# PIC18f26k40_TPLinkBackpack.net
KiCad netlist of a schematic drawn in EAGLE
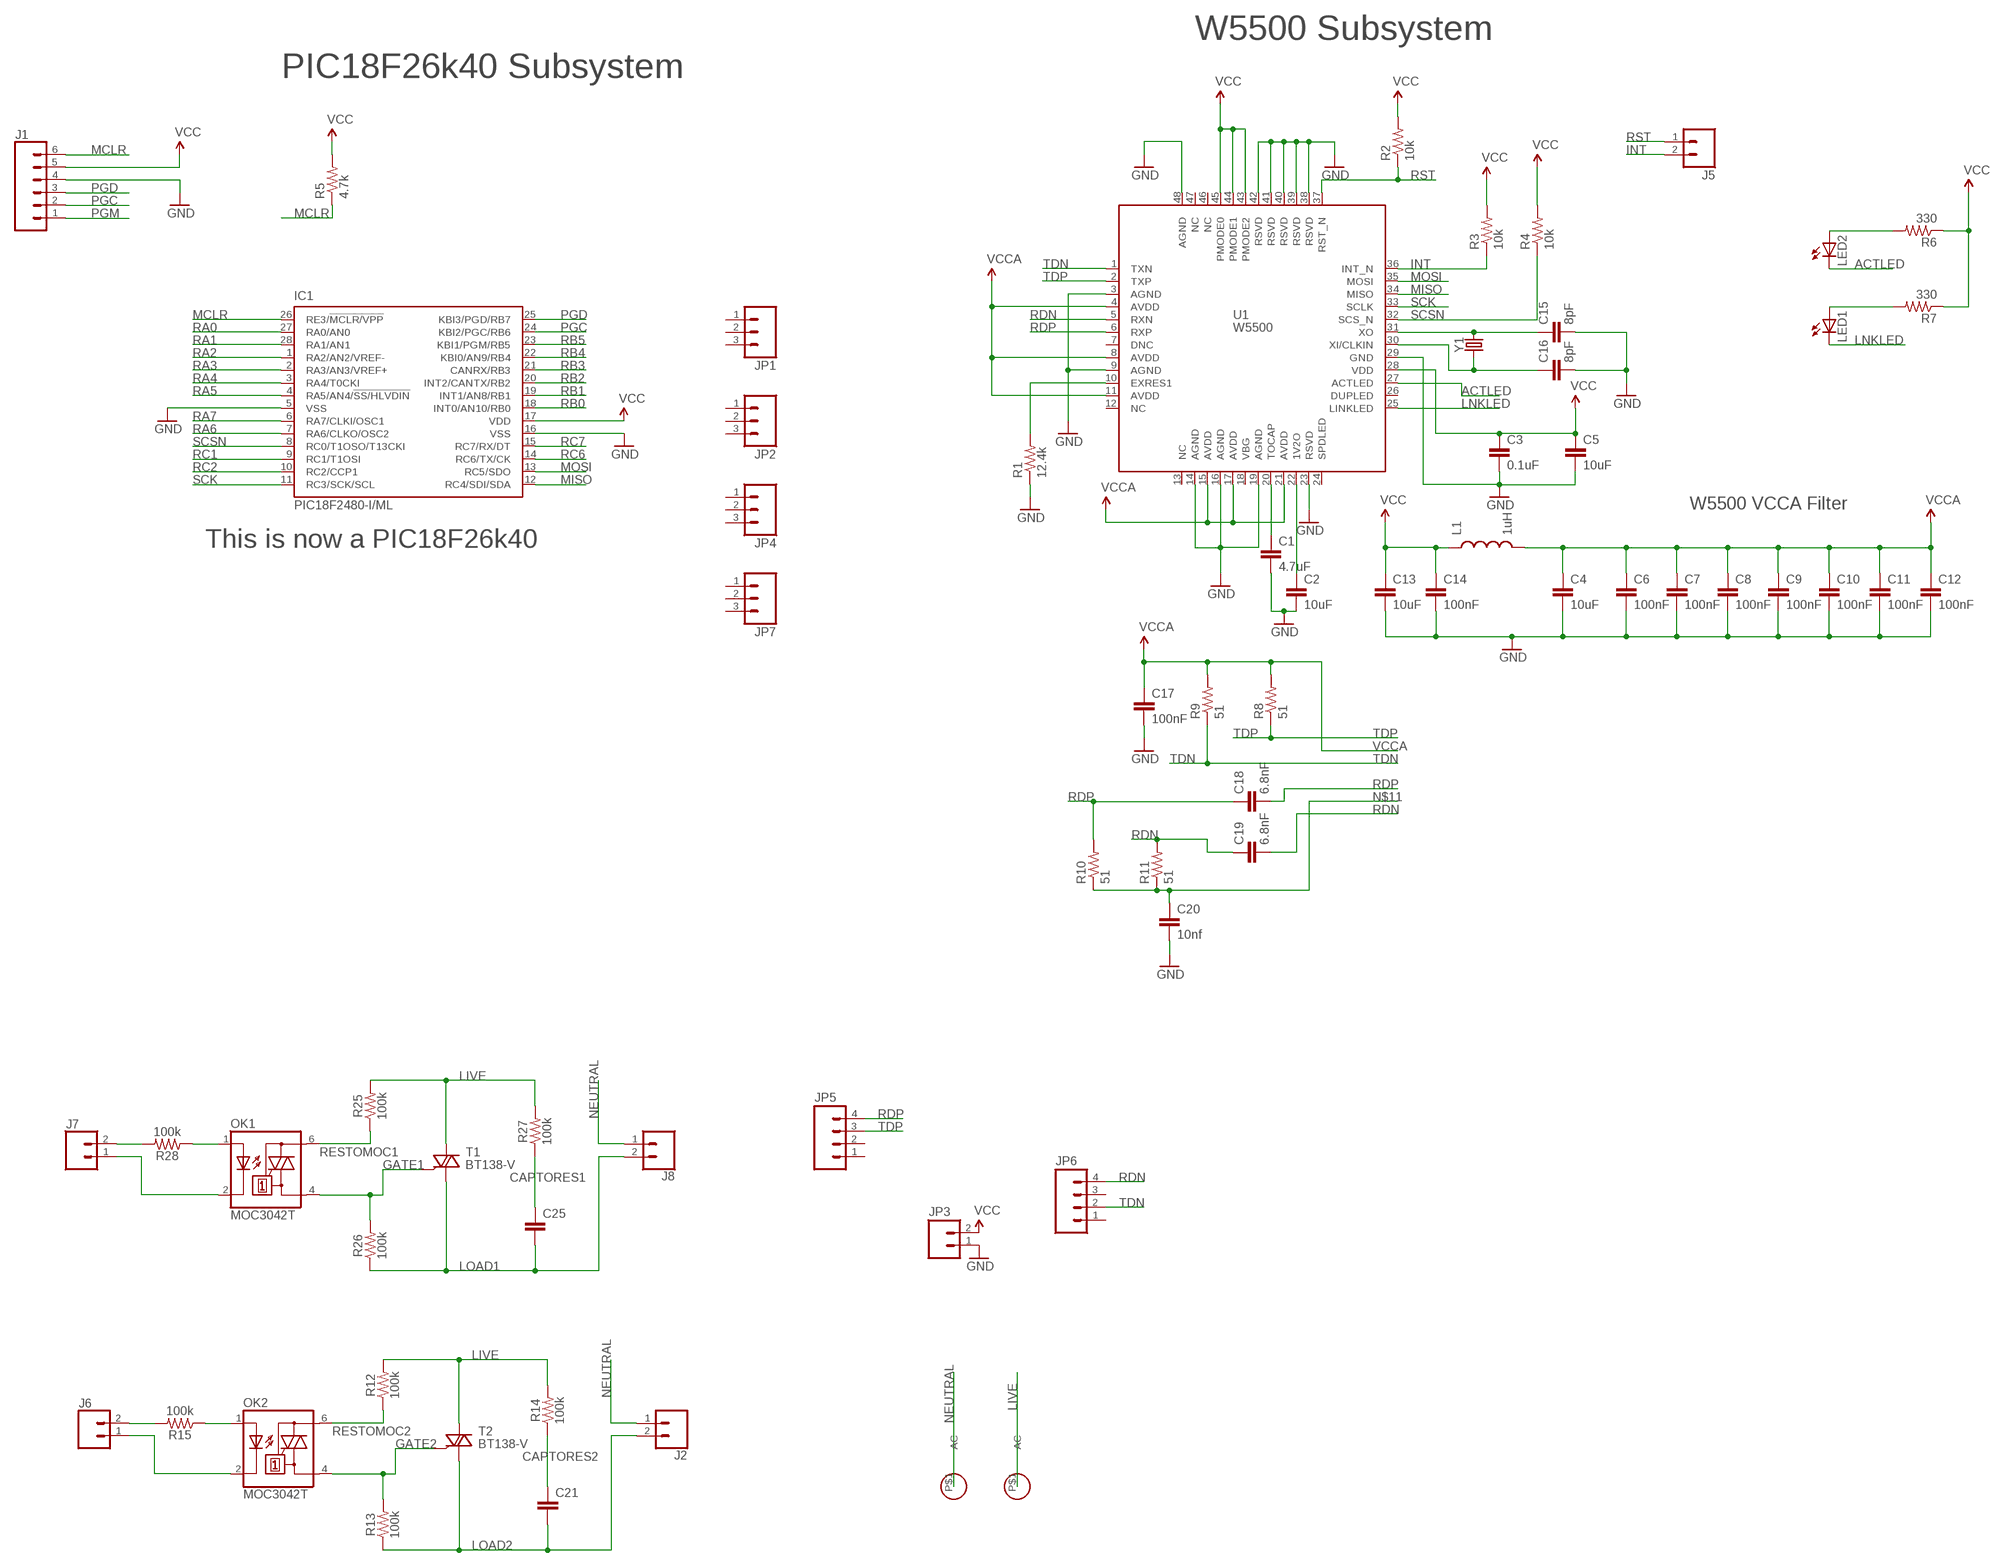
[diagram p0: schematic, sheet 1]

(export (version "E")
  (design (tool "Eeschema 10.0.6"))
  (components
    (comp (ref "AC_L")
      (value "AC_BLADE")
      (footprint "eagle-import:AC_BLADE")
      (libsource (lib "eagle-import") (part "AC_BLADE"))
    )
    (comp (ref "AC_N")
      (value "AC_BLADE")
      (footprint "eagle-import:AC_BLADE")
      (libsource (lib "eagle-import") (part "AC_BLADE"))
    )
    (comp (ref "C1")
      (value "4.7uF")
      (footprint "eagle-import:0603-CAP")
      (libsource (lib "eagle-import") (part "SparkFun-Passives_CAP0603-CAP"))
    )
    (comp (ref "C2")
      (value "10uF")
      (footprint "eagle-import:0603-CAP")
      (libsource (lib "eagle-import") (part "SparkFun-Passives_CAP0603-CAP"))
    )
    (comp (ref "C3")
      (value "0.1uF")
      (footprint "eagle-import:0603-CAP")
      (libsource (lib "eagle-import") (part "SparkFun-Passives_CAP0603-CAP"))
    )
    (comp (ref "C4")
      (value "10uF")
      (footprint "eagle-import:0603-CAP")
      (libsource (lib "eagle-import") (part "SparkFun-Passives_CAP0603-CAP"))
    )
    (comp (ref "C5")
      (value "10uF")
      (footprint "eagle-import:0603-CAP")
      (libsource (lib "eagle-import") (part "SparkFun-Passives_CAP0603-CAP"))
    )
    (comp (ref "C6")
      (value "100nF")
      (footprint "eagle-import:0603-CAP")
      (libsource (lib "eagle-import") (part "SparkFun-Passives_CAP0603-CAP"))
    )
    (comp (ref "C7")
      (value "100nF")
      (footprint "eagle-import:0603-CAP")
      (libsource (lib "eagle-import") (part "SparkFun-Passives_CAP0603-CAP"))
    )
    (comp (ref "C8")
      (value "100nF")
      (footprint "eagle-import:0603-CAP")
      (libsource (lib "eagle-import") (part "SparkFun-Passives_CAP0603-CAP"))
    )
    (comp (ref "C9")
      (value "100nF")
      (footprint "eagle-import:0603-CAP")
      (libsource (lib "eagle-import") (part "SparkFun-Passives_CAP0603-CAP"))
    )
    (comp (ref "C10")
      (value "100nF")
      (footprint "eagle-import:0603-CAP")
      (libsource (lib "eagle-import") (part "SparkFun-Passives_CAP0603-CAP"))
    )
    (comp (ref "C11")
      (value "100nF")
      (footprint "eagle-import:0603-CAP")
      (libsource (lib "eagle-import") (part "SparkFun-Passives_CAP0603-CAP"))
    )
    (comp (ref "C12")
      (value "100nF")
      (footprint "eagle-import:0603-CAP")
      (libsource (lib "eagle-import") (part "SparkFun-Passives_CAP0603-CAP"))
    )
    (comp (ref "C13")
      (value "10uF")
      (footprint "eagle-import:0603-CAP")
      (libsource (lib "eagle-import") (part "SparkFun-Passives_CAP0603-CAP"))
    )
    (comp (ref "C14")
      (value "100nF")
      (footprint "eagle-import:0603-CAP")
      (libsource (lib "eagle-import") (part "SparkFun-Passives_CAP0603-CAP"))
    )
    (comp (ref "C15")
      (value "8pF")
      (footprint "eagle-import:0603-CAP")
      (libsource (lib "eagle-import") (part "SparkFun-Passives_CAP0603-CAP"))
    )
    (comp (ref "C16")
      (value "8pF")
      (footprint "eagle-import:0603-CAP")
      (libsource (lib "eagle-import") (part "SparkFun-Passives_CAP0603-CAP"))
    )
    (comp (ref "C17")
      (value "100nF")
      (footprint "eagle-import:0603-CAP")
      (libsource (lib "eagle-import") (part "SparkFun-Passives_CAP0603-CAP"))
    )
    (comp (ref "C18")
      (value "6.8nF")
      (footprint "eagle-import:0603-CAP")
      (libsource (lib "eagle-import") (part "SparkFun-Passives_CAP0603-CAP"))
    )
    (comp (ref "C19")
      (value "6.8nF")
      (footprint "eagle-import:0603-CAP")
      (libsource (lib "eagle-import") (part "SparkFun-Passives_CAP0603-CAP"))
    )
    (comp (ref "C20")
      (value "10nf")
      (footprint "eagle-import:0603-CAP")
      (libsource (lib "eagle-import") (part "SparkFun-Passives_CAP0603-CAP"))
    )
    (comp (ref "C21")
      (value "CAP0603-CAP")
      (footprint "eagle-import:0603-CAP")
      (libsource (lib "eagle-import") (part "CAP0603-CAP"))
    )
    (comp (ref "C25")
      (value "CAP0603-CAP")
      (footprint "eagle-import:0603-CAP")
      (libsource (lib "eagle-import") (part "CAP0603-CAP"))
    )
    (comp (ref "IC1")
      (value "PIC18F2480-I/ML")
      (footprint "eagle-import:QFN28-ML_6X6MM")
      (fields (field (name "MF") "MICROCHIP"))
      (libsource (lib "eagle-import") (part "PIC18F280-I/ML4"))
    )
    (comp (ref "J1")
      (value "CONN_06NO_SILK_FEMALE_PTH")
      (footprint "eagle-import:1X06_NO_SILK")
      (libsource (lib "eagle-import") (part "CONN_06NO_SILK_FEMALE_PTH"))
    )
    (comp (ref "J2")
      (value "CONN_025MM")
      (footprint "eagle-import:SCREWTERMINAL-5MM-2")
      (libsource (lib "eagle-import") (part "CONN_025MM"))
    )
    (comp (ref "J5")
      (value "M02PTH")
      (footprint "eagle-import:1X02@1")
      (libsource (lib "eagle-import") (part "M02PTH"))
    )
    (comp (ref "J6")
      (value "CONN_02")
      (footprint "eagle-import:1X02")
      (libsource (lib "eagle-import") (part "CONN_02"))
    )
    (comp (ref "J7")
      (value "CONN_02")
      (footprint "eagle-import:1X02")
      (libsource (lib "eagle-import") (part "CONN_02"))
    )
    (comp (ref "J8")
      (value "CONN_025MM")
      (footprint "eagle-import:SCREWTERMINAL-5MM-2")
      (libsource (lib "eagle-import") (part "CONN_025MM"))
    )
    (comp (ref "JP1")
      (value "M03LONGPADS")
      (footprint "eagle-import:1X03_LONGPADS")
      (libsource (lib "eagle-import") (part "M03LONGPADS"))
    )
    (comp (ref "JP2")
      (value "M03LONGPADS")
      (footprint "eagle-import:1X03_LONGPADS")
      (libsource (lib "eagle-import") (part "M03LONGPADS"))
    )
    (comp (ref "JP3")
      (value "M021X02_NO_SILK")
      (footprint "eagle-import:1X02_NO_SILK@1")
      (libsource (lib "eagle-import") (part "M021X02_NO_SILK"))
    )
    (comp (ref "JP4")
      (value "M03LONGPADS")
      (footprint "eagle-import:1X03_LONGPADS")
      (libsource (lib "eagle-import") (part "M03LONGPADS"))
    )
    (comp (ref "JP5")
      (value "M04NO_SILK_ALL_ROUND")
      (footprint "eagle-import:1X04_NO_SILK_ALL_ROUND")
      (libsource (lib "eagle-import") (part "M04NO_SILK_ALL_ROUND"))
    )
    (comp (ref "JP6")
      (value "M04NO_SILK_ALL_ROUND")
      (footprint "eagle-import:1X04_NO_SILK_ALL_ROUND")
      (libsource (lib "eagle-import") (part "M04NO_SILK_ALL_ROUND"))
    )
    (comp (ref "JP7")
      (value "M03LONGPADS")
      (footprint "eagle-import:1X03_LONGPADS")
      (libsource (lib "eagle-import") (part "M03LONGPADS"))
    )
    (comp (ref "L1")
      (value "1uH")
      (footprint "eagle-import:0603")
      (libsource (lib "eagle-import") (part "INDUCTOR0603"))
    )
    (comp (ref "LED1")
      (value "LEDCHIP-LED0805")
      (footprint "eagle-import:CHIP-LED0805")
      (libsource (lib "eagle-import") (part "LEDCHIP-LED0805"))
    )
    (comp (ref "LED2")
      (value "LEDCHIP-LED0805")
      (footprint "eagle-import:CHIP-LED0805")
      (libsource (lib "eagle-import") (part "LEDCHIP-LED0805"))
    )
    (comp (ref "OK1")
      (value "MOC3042T")
      (footprint "eagle-import:DIL06B")
      (libsource (lib "eagle-import") (part "MOC30T42"))
    )
    (comp (ref "OK2")
      (value "MOC3042T")
      (footprint "eagle-import:DIL06B")
      (libsource (lib "eagle-import") (part "MOC30T42"))
    )
    (comp (ref "R1")
      (value "12.4k")
      (footprint "eagle-import:0603-RES")
      (libsource (lib "eagle-import") (part "RESISTOR0603-RES"))
    )
    (comp (ref "R2")
      (value "10k")
      (footprint "eagle-import:0603-RES")
      (libsource (lib "eagle-import") (part "RESISTOR0603-RES"))
    )
    (comp (ref "R3")
      (value "10k")
      (footprint "eagle-import:0603-RES")
      (libsource (lib "eagle-import") (part "RESISTOR0603-RES"))
    )
    (comp (ref "R4")
      (value "10k")
      (footprint "eagle-import:0603-RES")
      (libsource (lib "eagle-import") (part "RESISTOR0603-RES"))
    )
    (comp (ref "R5")
      (value "4.7k")
      (footprint "eagle-import:0603-RES")
      (libsource (lib "eagle-import") (part "RESISTOR0603-RES"))
    )
    (comp (ref "R6")
      (value "330")
      (footprint "eagle-import:0603-RES")
      (libsource (lib "eagle-import") (part "RESISTOR0603-RES"))
    )
    (comp (ref "R7")
      (value "330")
      (footprint "eagle-import:0603-RES")
      (libsource (lib "eagle-import") (part "RESISTOR0603-RES"))
    )
    (comp (ref "R8")
      (value "51")
      (footprint "eagle-import:0603-RES")
      (libsource (lib "eagle-import") (part "RESISTOR0603-RES"))
    )
    (comp (ref "R9")
      (value "51")
      (footprint "eagle-import:0603-RES")
      (libsource (lib "eagle-import") (part "RESISTOR0603-RES"))
    )
    (comp (ref "R10")
      (value "51")
      (footprint "eagle-import:0603-RES")
      (libsource (lib "eagle-import") (part "RESISTOR0603-RES"))
    )
    (comp (ref "R11")
      (value "51")
      (footprint "eagle-import:0603-RES")
      (libsource (lib "eagle-import") (part "RESISTOR0603-RES"))
    )
    (comp (ref "R12")
      (value "100k")
      (footprint "eagle-import:0603")
      (libsource (lib "eagle-import") (part "100KOHM-0603-1/10W-1%"))
    )
    (comp (ref "R13")
      (value "100k")
      (footprint "eagle-import:0603")
      (libsource (lib "eagle-import") (part "100KOHM-0603-1/10W-1%"))
    )
    (comp (ref "R14")
      (value "100k")
      (footprint "eagle-import:0603")
      (libsource (lib "eagle-import") (part "100KOHM-0603-1/10W-1%"))
    )
    (comp (ref "R15")
      (value "100k")
      (footprint "eagle-import:0603")
      (libsource (lib "eagle-import") (part "100KOHM-0603-1/10W-1%"))
    )
    (comp (ref "R25")
      (value "100k")
      (footprint "eagle-import:0603")
      (libsource (lib "eagle-import") (part "100KOHM-0603-1/10W-1%"))
    )
    (comp (ref "R26")
      (value "100k")
      (footprint "eagle-import:0603")
      (libsource (lib "eagle-import") (part "100KOHM-0603-1/10W-1%"))
    )
    (comp (ref "R27")
      (value "100k")
      (footprint "eagle-import:0603")
      (libsource (lib "eagle-import") (part "100KOHM-0603-1/10W-1%"))
    )
    (comp (ref "R28")
      (value "100k")
      (footprint "eagle-import:0603")
      (libsource (lib "eagle-import") (part "100KOHM-0603-1/10W-1%"))
    )
    (comp (ref "T1")
      (value "BT138-V")
      (footprint "eagle-import:TO220BV")
      (libsource (lib "eagle-import") (part "BT138-V"))
    )
    (comp (ref "T2")
      (value "BT138-V")
      (footprint "eagle-import:TO220BV")
      (libsource (lib "eagle-import") (part "BT138-V"))
    )
    (comp (ref "U1")
      (value "W5500")
      (footprint "eagle-import:W5500")
      (libsource (lib "eagle-import") (part "W5500"))
    )
    (comp (ref "Y1")
      (value "CRYSTALSMD-3.2X2.5")
      (footprint "eagle-import:CRYSTAL-SMD-3.2X2.5MM")
      (libsource (lib "eagle-import") (part "CRYSTALSMD-3.2X2.5"))
    )
  )
  (nets
    (net (code "1") (name "/ACTLED") (class "Default")
      (node (ref "LED2") (pin "C") (pinfunction "C_C") (pintype "passive"))
      (node (ref "U1") (pin "27") (pinfunction "ACTLED_27") (pintype "passive"))
    )
    (net (code "2") (name "/CAPTORES1") (class "Default")
      (node (ref "C25") (pin "1") (pinfunction "1_1") (pintype "passive"))
      (node (ref "R27") (pin "1") (pinfunction "1_1") (pintype "passive"))
    )
    (net (code "3") (name "/CAPTORES2") (class "Default")
      (node (ref "C21") (pin "1") (pinfunction "1_1") (pintype "passive"))
      (node (ref "R14") (pin "1") (pinfunction "1_1") (pintype "passive"))
    )
    (net (code "4") (name "/GATE1") (class "Default")
      (node (ref "OK1") (pin "4") (pinfunction "A1_4") (pintype "passive"))
      (node (ref "R26") (pin "2") (pinfunction "2_2") (pintype "passive"))
      (node (ref "T1") (pin "G") (pinfunction "G_G") (pintype "passive"))
    )
    (net (code "5") (name "/GATE2") (class "Default")
      (node (ref "OK2") (pin "4") (pinfunction "A1_4") (pintype "passive"))
      (node (ref "R13") (pin "2") (pinfunction "2_2") (pintype "passive"))
      (node (ref "T2") (pin "G") (pinfunction "G_G") (pintype "passive"))
    )
    (net (code "6") (name "/INT") (class "Default")
      (node (ref "J5") (pin "2") (pinfunction "2_2") (pintype "passive"))
      (node (ref "R3") (pin "1") (pinfunction "1_1") (pintype "passive"))
      (node (ref "U1") (pin "36") (pinfunction "INT_N_36") (pintype "passive"))
    )
    (net (code "7") (name "/LIVE") (class "Default")
      (node (ref "AC_L") (pin "P$1") (pinfunction "AC_P$1") (pintype "bidirectional"))
      (node (ref "R12") (pin "2") (pinfunction "2_2") (pintype "passive"))
      (node (ref "R14") (pin "2") (pinfunction "2_2") (pintype "passive"))
      (node (ref "R25") (pin "2") (pinfunction "2_2") (pintype "passive"))
      (node (ref "R27") (pin "2") (pinfunction "2_2") (pintype "passive"))
      (node (ref "T1") (pin "T2") (pinfunction "A2_T2") (pintype "passive"))
      (node (ref "T2") (pin "T2") (pinfunction "A2_T2") (pintype "passive"))
    )
    (net (code "8") (name "/LNKLED") (class "Default")
      (node (ref "LED1") (pin "C") (pinfunction "C_C") (pintype "passive"))
      (node (ref "U1") (pin "25") (pinfunction "LINKLED_25") (pintype "passive"))
    )
    (net (code "9") (name "/LOAD1") (class "Default")
      (node (ref "C25") (pin "2") (pinfunction "2_2") (pintype "passive"))
      (node (ref "J8") (pin "2") (pinfunction "2_2") (pintype "passive"))
      (node (ref "R26") (pin "1") (pinfunction "1_1") (pintype "passive"))
      (node (ref "T1") (pin "T1") (pinfunction "A1_T1") (pintype "passive"))
    )
    (net (code "10") (name "/LOAD2") (class "Default")
      (node (ref "C21") (pin "2") (pinfunction "2_2") (pintype "passive"))
      (node (ref "J2") (pin "2") (pinfunction "2_2") (pintype "passive"))
      (node (ref "R13") (pin "1") (pinfunction "1_1") (pintype "passive"))
      (node (ref "T2") (pin "T1") (pinfunction "A1_T1") (pintype "passive"))
    )
    (net (code "11") (name "/MCLR") (class "Default")
      (node (ref "IC1") (pin "26") (pinfunction "RE3/~{MCLR/VPP}_26") (pintype "input"))
      (node (ref "J1") (pin "6") (pinfunction "6_6") (pintype "passive"))
      (node (ref "R5") (pin "1") (pinfunction "1_1") (pintype "passive"))
    )
    (net (code "12") (name "/MISO") (class "Default")
      (node (ref "IC1") (pin "12") (pinfunction "RC4/SDI/SDA_12") (pintype "bidirectional"))
      (node (ref "U1") (pin "34") (pinfunction "MISO_34") (pintype "passive"))
    )
    (net (code "13") (name "/MOSI") (class "Default")
      (node (ref "IC1") (pin "13") (pinfunction "RC5/SDO_13") (pintype "bidirectional"))
      (node (ref "U1") (pin "35") (pinfunction "MOSI_35") (pintype "passive"))
    )
    (net (code "14") (name "/N$11") (class "Default")
      (node (ref "C20") (pin "1") (pinfunction "1_1") (pintype "passive"))
      (node (ref "R10") (pin "1") (pinfunction "1_1") (pintype "passive"))
      (node (ref "R11") (pin "1") (pinfunction "1_1") (pintype "passive"))
    )
    (net (code "15") (name "/NEUTRAL") (class "Default")
      (node (ref "AC_N") (pin "P$1") (pinfunction "AC_P$1") (pintype "bidirectional"))
      (node (ref "J2") (pin "1") (pinfunction "1_1") (pintype "passive"))
      (node (ref "J8") (pin "1") (pinfunction "1_1") (pintype "passive"))
    )
    (net (code "16") (name "/PGC") (class "Default")
      (node (ref "IC1") (pin "24") (pinfunction "KBI2/PGC/RB6_24") (pintype "bidirectional"))
      (node (ref "J1") (pin "2") (pinfunction "2_2") (pintype "passive"))
    )
    (net (code "17") (name "/PGD") (class "Default")
      (node (ref "IC1") (pin "25") (pinfunction "KBI3/PGD/RB7_25") (pintype "bidirectional"))
      (node (ref "J1") (pin "3") (pinfunction "3_3") (pintype "passive"))
    )
    (net (code "18") (name "/PGM") (class "Default")
      (node (ref "J1") (pin "1") (pinfunction "1_1") (pintype "passive"))
    )
    (net (code "19") (name "/RA0") (class "Default")
      (node (ref "IC1") (pin "27") (pinfunction "RA0/AN0_27") (pintype "bidirectional"))
    )
    (net (code "20") (name "/RA1") (class "Default")
      (node (ref "IC1") (pin "28") (pinfunction "RA1/AN1_28") (pintype "bidirectional"))
    )
    (net (code "21") (name "/RA2") (class "Default")
      (node (ref "IC1") (pin "1") (pinfunction "RA2/AN2/VREF-_1") (pintype "bidirectional"))
    )
    (net (code "22") (name "/RA3") (class "Default")
      (node (ref "IC1") (pin "2") (pinfunction "RA3/AN3/VREF+_2") (pintype "bidirectional"))
    )
    (net (code "23") (name "/RA4") (class "Default")
      (node (ref "IC1") (pin "3") (pinfunction "RA4/T0CKI_3") (pintype "bidirectional"))
    )
    (net (code "24") (name "/RA5") (class "Default")
      (node (ref "IC1") (pin "4") (pinfunction "RA5/AN4/~{SS/HLVDIN}_4") (pintype "bidirectional"))
    )
    (net (code "25") (name "/RA6") (class "Default")
      (node (ref "IC1") (pin "7") (pinfunction "RA6/CLKO/OSC2_7") (pintype "output"))
    )
    (net (code "26") (name "/RA7") (class "Default")
      (node (ref "IC1") (pin "6") (pinfunction "RA7/CLKI/OSC1_6") (pintype "input"))
    )
    (net (code "27") (name "/RB0") (class "Default")
      (node (ref "IC1") (pin "18") (pinfunction "INT0/AN10/RB0_18") (pintype "bidirectional"))
    )
    (net (code "28") (name "/RB1") (class "Default")
      (node (ref "IC1") (pin "19") (pinfunction "INT1/AN8/RB1_19") (pintype "bidirectional"))
    )
    (net (code "29") (name "/RB2") (class "Default")
      (node (ref "IC1") (pin "20") (pinfunction "INT2/CANTX/RB2_20") (pintype "bidirectional"))
    )
    (net (code "30") (name "/RB3") (class "Default")
      (node (ref "IC1") (pin "21") (pinfunction "CANRX/RB3_21") (pintype "bidirectional"))
    )
    (net (code "31") (name "/RB4") (class "Default")
      (node (ref "IC1") (pin "22") (pinfunction "KBI0/AN9/RB4_22") (pintype "bidirectional"))
    )
    (net (code "32") (name "/RB5") (class "Default")
      (node (ref "IC1") (pin "23") (pinfunction "KBI1/PGM/RB5_23") (pintype "bidirectional"))
    )
    (net (code "33") (name "/RC1") (class "Default")
      (node (ref "IC1") (pin "9") (pinfunction "RC1/T1OSI_9") (pintype "bidirectional"))
    )
    (net (code "34") (name "/RC2") (class "Default")
      (node (ref "IC1") (pin "10") (pinfunction "RC2/CCP1_10") (pintype "bidirectional"))
    )
    (net (code "35") (name "/RC6") (class "Default")
      (node (ref "IC1") (pin "14") (pinfunction "RC6/TX/CK_14") (pintype "bidirectional"))
    )
    (net (code "36") (name "/RC7") (class "Default")
      (node (ref "IC1") (pin "15") (pinfunction "RC7/RX/DT_15") (pintype "bidirectional"))
    )
    (net (code "37") (name "/RDN") (class "Default")
      (node (ref "C19") (pin "1") (pinfunction "1_1") (pintype "passive"))
      (node (ref "C19") (pin "2") (pinfunction "2_2") (pintype "passive"))
      (node (ref "JP6") (pin "4") (pinfunction "4_4") (pintype "passive"))
      (node (ref "R11") (pin "2") (pinfunction "2_2") (pintype "passive"))
      (node (ref "U1") (pin "5") (pinfunction "RXN_5") (pintype "passive"))
    )
    (net (code "38") (name "/RDP") (class "Default")
      (node (ref "C18") (pin "1") (pinfunction "1_1") (pintype "passive"))
      (node (ref "C18") (pin "2") (pinfunction "2_2") (pintype "passive"))
      (node (ref "JP5") (pin "4") (pinfunction "4_4") (pintype "passive"))
      (node (ref "R10") (pin "2") (pinfunction "2_2") (pintype "passive"))
      (node (ref "U1") (pin "6") (pinfunction "RXP_6") (pintype "passive"))
    )
    (net (code "39") (name "/RESTOMOC1") (class "Default")
      (node (ref "OK1") (pin "6") (pinfunction "A2_6") (pintype "passive"))
      (node (ref "R25") (pin "1") (pinfunction "1_1") (pintype "passive"))
    )
    (net (code "40") (name "/RESTOMOC2") (class "Default")
      (node (ref "OK2") (pin "6") (pinfunction "A2_6") (pintype "passive"))
      (node (ref "R12") (pin "1") (pinfunction "1_1") (pintype "passive"))
    )
    (net (code "41") (name "/RST") (class "Default")
      (node (ref "J5") (pin "1") (pinfunction "1_1") (pintype "passive"))
      (node (ref "R2") (pin "1") (pinfunction "1_1") (pintype "passive"))
      (node (ref "U1") (pin "37") (pinfunction "RST_N_37") (pintype "passive"))
    )
    (net (code "42") (name "/SCK") (class "Default")
      (node (ref "IC1") (pin "11") (pinfunction "RC3/SCK/SCL_11") (pintype "bidirectional"))
      (node (ref "U1") (pin "33") (pinfunction "SCLK_33") (pintype "passive"))
    )
    (net (code "43") (name "/SCSN") (class "Default")
      (node (ref "IC1") (pin "8") (pinfunction "RC0/T1OSO/T13CKI_8") (pintype "bidirectional"))
      (node (ref "R4") (pin "1") (pinfunction "1_1") (pintype "passive"))
      (node (ref "U1") (pin "32") (pinfunction "SCS_N_32") (pintype "passive"))
    )
    (net (code "44") (name "/TDN") (class "Default")
      (node (ref "JP6") (pin "2") (pinfunction "2_2") (pintype "passive"))
      (node (ref "R9") (pin "1") (pinfunction "1_1") (pintype "passive"))
      (node (ref "U1") (pin "1") (pinfunction "TXN_1") (pintype "passive"))
    )
    (net (code "45") (name "/TDP") (class "Default")
      (node (ref "JP5") (pin "3") (pinfunction "3_3") (pintype "passive"))
      (node (ref "R8") (pin "1") (pinfunction "1_1") (pintype "passive"))
      (node (ref "U1") (pin "2") (pinfunction "TXP_2") (pintype "passive"))
    )
    (net (code "46") (name "GND") (class "Default")
      (node (ref "C1") (pin "2") (pinfunction "2_2") (pintype "passive"))
      (node (ref "C10") (pin "2") (pinfunction "2_2") (pintype "passive"))
      (node (ref "C11") (pin "2") (pinfunction "2_2") (pintype "passive"))
      (node (ref "C12") (pin "2") (pinfunction "2_2") (pintype "passive"))
      (node (ref "C13") (pin "2") (pinfunction "2_2") (pintype "passive"))
      (node (ref "C14") (pin "2") (pinfunction "2_2") (pintype "passive"))
      (node (ref "C15") (pin "2") (pinfunction "2_2") (pintype "passive"))
      (node (ref "C16") (pin "2") (pinfunction "2_2") (pintype "passive"))
      (node (ref "C17") (pin "2") (pinfunction "2_2") (pintype "passive"))
      (node (ref "C2") (pin "2") (pinfunction "2_2") (pintype "passive"))
      (node (ref "C20") (pin "2") (pinfunction "2_2") (pintype "passive"))
      (node (ref "C3") (pin "2") (pinfunction "2_2") (pintype "passive"))
      (node (ref "C4") (pin "2") (pinfunction "2_2") (pintype "passive"))
      (node (ref "C5") (pin "2") (pinfunction "2_2") (pintype "passive"))
      (node (ref "C6") (pin "2") (pinfunction "2_2") (pintype "passive"))
      (node (ref "C7") (pin "2") (pinfunction "2_2") (pintype "passive"))
      (node (ref "C8") (pin "2") (pinfunction "2_2") (pintype "passive"))
      (node (ref "C9") (pin "2") (pinfunction "2_2") (pintype "passive"))
      (node (ref "IC1") (pin "16") (pinfunction "VSS_16") (pintype "power_in"))
      (node (ref "IC1") (pin "5") (pinfunction "VSS_5") (pintype "power_in"))
      (node (ref "J1") (pin "4") (pinfunction "4_4") (pintype "passive"))
      (node (ref "JP3") (pin "1") (pinfunction "1_1") (pintype "passive"))
      (node (ref "R1") (pin "1") (pinfunction "1_1") (pintype "passive"))
      (node (ref "U1") (pin "14") (pinfunction "AGND_14") (pintype "passive"))
      (node (ref "U1") (pin "16") (pinfunction "AGND_16") (pintype "passive"))
      (node (ref "U1") (pin "19") (pinfunction "AGND_19") (pintype "passive"))
      (node (ref "U1") (pin "23") (pinfunction "RSVD_23") (pintype "passive"))
      (node (ref "U1") (pin "29") (pinfunction "GND_29") (pintype "passive"))
      (node (ref "U1") (pin "3") (pinfunction "AGND_3") (pintype "passive"))
      (node (ref "U1") (pin "38") (pinfunction "RSVD_38") (pintype "passive"))
      (node (ref "U1") (pin "39") (pinfunction "RSVD_39") (pintype "passive"))
      (node (ref "U1") (pin "40") (pinfunction "RSVD_40") (pintype "passive"))
      (node (ref "U1") (pin "41") (pinfunction "RSVD_41") (pintype "passive"))
      (node (ref "U1") (pin "42") (pinfunction "RSVD_42") (pintype "passive"))
      (node (ref "U1") (pin "48") (pinfunction "AGND_48") (pintype "passive"))
      (node (ref "U1") (pin "9") (pinfunction "AGND_9") (pintype "passive"))
    )
    (net (code "47") (name "Net-(J6-Pad2)") (class "Default")
      (node (ref "J6") (pin "2") (pinfunction "2_2") (pintype "passive"))
      (node (ref "R15") (pin "2") (pinfunction "2_2") (pintype "passive"))
    )
    (net (code "48") (name "Net-(J7-Pad2)") (class "Default")
      (node (ref "J7") (pin "2") (pinfunction "2_2") (pintype "passive"))
      (node (ref "R28") (pin "2") (pinfunction "2_2") (pintype "passive"))
    )
    (net (code "49") (name "Net-(LED1-PadA)") (class "Default")
      (node (ref "LED1") (pin "A") (pinfunction "A_A") (pintype "passive"))
      (node (ref "R7") (pin "2") (pinfunction "2_2") (pintype "passive"))
    )
    (net (code "50") (name "Net-(LED2-PadA)") (class "Default")
      (node (ref "LED2") (pin "A") (pinfunction "A_A") (pintype "passive"))
      (node (ref "R6") (pin "2") (pinfunction "2_2") (pintype "passive"))
    )
    (net (code "51") (name "Net-(OK1-A)") (class "Default")
      (node (ref "OK1") (pin "1") (pinfunction "A_1") (pintype "passive"))
      (node (ref "R28") (pin "1") (pinfunction "1_1") (pintype "passive"))
    )
    (net (code "52") (name "Net-(OK1-C)") (class "Default")
      (node (ref "J7") (pin "1") (pinfunction "1_1") (pintype "passive"))
      (node (ref "OK1") (pin "2") (pinfunction "C_2") (pintype "passive"))
    )
    (net (code "53") (name "Net-(OK2-A)") (class "Default")
      (node (ref "OK2") (pin "1") (pinfunction "A_1") (pintype "passive"))
      (node (ref "R15") (pin "1") (pinfunction "1_1") (pintype "passive"))
    )
    (net (code "54") (name "Net-(OK2-C)") (class "Default")
      (node (ref "J6") (pin "1") (pinfunction "1_1") (pintype "passive"))
      (node (ref "OK2") (pin "2") (pinfunction "C_2") (pintype "passive"))
    )
    (net (code "55") (name "Net-(U1-1V2O)") (class "Default")
      (node (ref "C2") (pin "1") (pinfunction "1_1") (pintype "passive"))
      (node (ref "U1") (pin "22") (pinfunction "1V2O_22") (pintype "passive"))
    )
    (net (code "56") (name "Net-(U1-EXRES1)") (class "Default")
      (node (ref "R1") (pin "2") (pinfunction "2_2") (pintype "passive"))
      (node (ref "U1") (pin "10") (pinfunction "EXRES1_10") (pintype "passive"))
    )
    (net (code "57") (name "Net-(U1-TOCAP)") (class "Default")
      (node (ref "C1") (pin "1") (pinfunction "1_1") (pintype "passive"))
      (node (ref "U1") (pin "20") (pinfunction "TOCAP_20") (pintype "passive"))
    )
    (net (code "58") (name "Net-(U1-XI{slash}CLKIN)") (class "Default")
      (node (ref "C16") (pin "1") (pinfunction "1_1") (pintype "passive"))
      (node (ref "U1") (pin "30") (pinfunction "XI/CLKIN_30") (pintype "passive"))
      (node (ref "Y1") (pin "1") (pinfunction "1_1") (pintype "passive"))
    )
    (net (code "59") (name "Net-(U1-XO)") (class "Default")
      (node (ref "C15") (pin "1") (pinfunction "1_1") (pintype "passive"))
      (node (ref "U1") (pin "31") (pinfunction "XO_31") (pintype "passive"))
      (node (ref "Y1") (pin "3") (pinfunction "2_3") (pintype "passive"))
    )
    (net (code "60") (name "VCC") (class "Default")
      (node (ref "C13") (pin "1") (pinfunction "1_1") (pintype "passive"))
      (node (ref "C14") (pin "1") (pinfunction "1_1") (pintype "passive"))
      (node (ref "C3") (pin "1") (pinfunction "1_1") (pintype "passive"))
      (node (ref "C5") (pin "1") (pinfunction "1_1") (pintype "passive"))
      (node (ref "IC1") (pin "17") (pinfunction "VDD_17") (pintype "power_in"))
      (node (ref "J1") (pin "5") (pinfunction "5_5") (pintype "passive"))
      (node (ref "JP3") (pin "2") (pinfunction "2_2") (pintype "passive"))
      (node (ref "L1") (pin "1") (pinfunction "1_1") (pintype "passive"))
      (node (ref "R2") (pin "2") (pinfunction "2_2") (pintype "passive"))
      (node (ref "R3") (pin "2") (pinfunction "2_2") (pintype "passive"))
      (node (ref "R4") (pin "2") (pinfunction "2_2") (pintype "passive"))
      (node (ref "R5") (pin "2") (pinfunction "2_2") (pintype "passive"))
      (node (ref "R6") (pin "1") (pinfunction "1_1") (pintype "passive"))
      (node (ref "R7") (pin "1") (pinfunction "1_1") (pintype "passive"))
      (node (ref "U1") (pin "28") (pinfunction "VDD_28") (pintype "passive"))
      (node (ref "U1") (pin "43") (pinfunction "PMODE2_43") (pintype "passive"))
      (node (ref "U1") (pin "44") (pinfunction "PMODE1_44") (pintype "passive"))
      (node (ref "U1") (pin "45") (pinfunction "PMODE0_45") (pintype "passive"))
    )
    (net (code "61") (name "VCCA") (class "Default")
      (node (ref "C10") (pin "1") (pinfunction "1_1") (pintype "passive"))
      (node (ref "C11") (pin "1") (pinfunction "1_1") (pintype "passive"))
      (node (ref "C12") (pin "1") (pinfunction "1_1") (pintype "passive"))
      (node (ref "C17") (pin "1") (pinfunction "1_1") (pintype "passive"))
      (node (ref "C4") (pin "1") (pinfunction "1_1") (pintype "passive"))
      (node (ref "C6") (pin "1") (pinfunction "1_1") (pintype "passive"))
      (node (ref "C7") (pin "1") (pinfunction "1_1") (pintype "passive"))
      (node (ref "C8") (pin "1") (pinfunction "1_1") (pintype "passive"))
      (node (ref "C9") (pin "1") (pinfunction "1_1") (pintype "passive"))
      (node (ref "L1") (pin "2") (pinfunction "2_2") (pintype "passive"))
      (node (ref "R8") (pin "2") (pinfunction "2_2") (pintype "passive"))
      (node (ref "R9") (pin "2") (pinfunction "2_2") (pintype "passive"))
      (node (ref "U1") (pin "11") (pinfunction "AVDD_11") (pintype "passive"))
      (node (ref "U1") (pin "15") (pinfunction "AVDD_15") (pintype "passive"))
      (node (ref "U1") (pin "17") (pinfunction "AVDD_17") (pintype "passive"))
      (node (ref "U1") (pin "21") (pinfunction "AVDD_21") (pintype "passive"))
      (node (ref "U1") (pin "4") (pinfunction "AVDD_4") (pintype "passive"))
      (node (ref "U1") (pin "8") (pinfunction "AVDD_8") (pintype "passive"))
    )
    (net (code "62") (name "unconnected-(JP1-Pad1)") (class "Default")
      (node (ref "JP1") (pin "1") (pinfunction "1_1") (pintype "passive"))
    )
    (net (code "63") (name "unconnected-(JP1-Pad2)") (class "Default")
      (node (ref "JP1") (pin "2") (pinfunction "2_2") (pintype "passive"))
    )
    (net (code "64") (name "unconnected-(JP1-Pad3)") (class "Default")
      (node (ref "JP1") (pin "3") (pinfunction "3_3") (pintype "passive"))
    )
    (net (code "65") (name "unconnected-(JP2-Pad1)") (class "Default")
      (node (ref "JP2") (pin "1") (pinfunction "1_1") (pintype "passive"))
    )
    (net (code "66") (name "unconnected-(JP2-Pad2)") (class "Default")
      (node (ref "JP2") (pin "2") (pinfunction "2_2") (pintype "passive"))
    )
    (net (code "67") (name "unconnected-(JP2-Pad3)") (class "Default")
      (node (ref "JP2") (pin "3") (pinfunction "3_3") (pintype "passive"))
    )
    (net (code "68") (name "unconnected-(JP4-Pad1)") (class "Default")
      (node (ref "JP4") (pin "1") (pinfunction "1_1") (pintype "passive"))
    )
    (net (code "69") (name "unconnected-(JP4-Pad2)") (class "Default")
      (node (ref "JP4") (pin "2") (pinfunction "2_2") (pintype "passive"))
    )
    (net (code "70") (name "unconnected-(JP4-Pad3)") (class "Default")
      (node (ref "JP4") (pin "3") (pinfunction "3_3") (pintype "passive"))
    )
    (net (code "71") (name "unconnected-(JP5-Pad1)") (class "Default")
      (node (ref "JP5") (pin "1") (pinfunction "1_1") (pintype "passive"))
    )
    (net (code "72") (name "unconnected-(JP5-Pad2)") (class "Default")
      (node (ref "JP5") (pin "2") (pinfunction "2_2") (pintype "passive"))
    )
    (net (code "73") (name "unconnected-(JP6-Pad1)") (class "Default")
      (node (ref "JP6") (pin "1") (pinfunction "1_1") (pintype "passive"))
    )
    (net (code "74") (name "unconnected-(JP6-Pad3)") (class "Default")
      (node (ref "JP6") (pin "3") (pinfunction "3_3") (pintype "passive"))
    )
    (net (code "75") (name "unconnected-(JP7-Pad1)") (class "Default")
      (node (ref "JP7") (pin "1") (pinfunction "1_1") (pintype "passive"))
    )
    (net (code "76") (name "unconnected-(JP7-Pad2)") (class "Default")
      (node (ref "JP7") (pin "2") (pinfunction "2_2") (pintype "passive"))
    )
    (net (code "77") (name "unconnected-(JP7-Pad3)") (class "Default")
      (node (ref "JP7") (pin "3") (pinfunction "3_3") (pintype "passive"))
    )
    (net (code "78") (name "unconnected-(U1-DNC-Pad7)") (class "Default")
      (node (ref "U1") (pin "7") (pinfunction "DNC_7") (pintype "passive"))
    )
    (net (code "79") (name "unconnected-(U1-DUPLED-Pad26)") (class "Default")
      (node (ref "U1") (pin "26") (pinfunction "DUPLED_26") (pintype "passive"))
    )
    (net (code "80") (name "unconnected-(U1-NC-Pad12)") (class "Default")
      (node (ref "U1") (pin "12") (pinfunction "NC_12") (pintype "passive"))
    )
    (net (code "81") (name "unconnected-(U1-NC-Pad13)") (class "Default")
      (node (ref "U1") (pin "13") (pinfunction "NC_13") (pintype "passive"))
    )
    (net (code "82") (name "unconnected-(U1-NC-Pad46)") (class "Default")
      (node (ref "U1") (pin "46") (pinfunction "NC_46") (pintype "passive"))
    )
    (net (code "83") (name "unconnected-(U1-NC-Pad47)") (class "Default")
      (node (ref "U1") (pin "47") (pinfunction "NC_47") (pintype "passive"))
    )
    (net (code "84") (name "unconnected-(U1-SPDLED-Pad24)") (class "Default")
      (node (ref "U1") (pin "24") (pinfunction "SPDLED_24") (pintype "passive"))
    )
    (net (code "85") (name "unconnected-(U1-VBG-Pad18)") (class "Default")
      (node (ref "U1") (pin "18") (pinfunction "VBG_18") (pintype "passive"))
    )
  )
)
